# Pixel1_0_0.net
KiCad netlist of a schematic drawn in Altium Designer
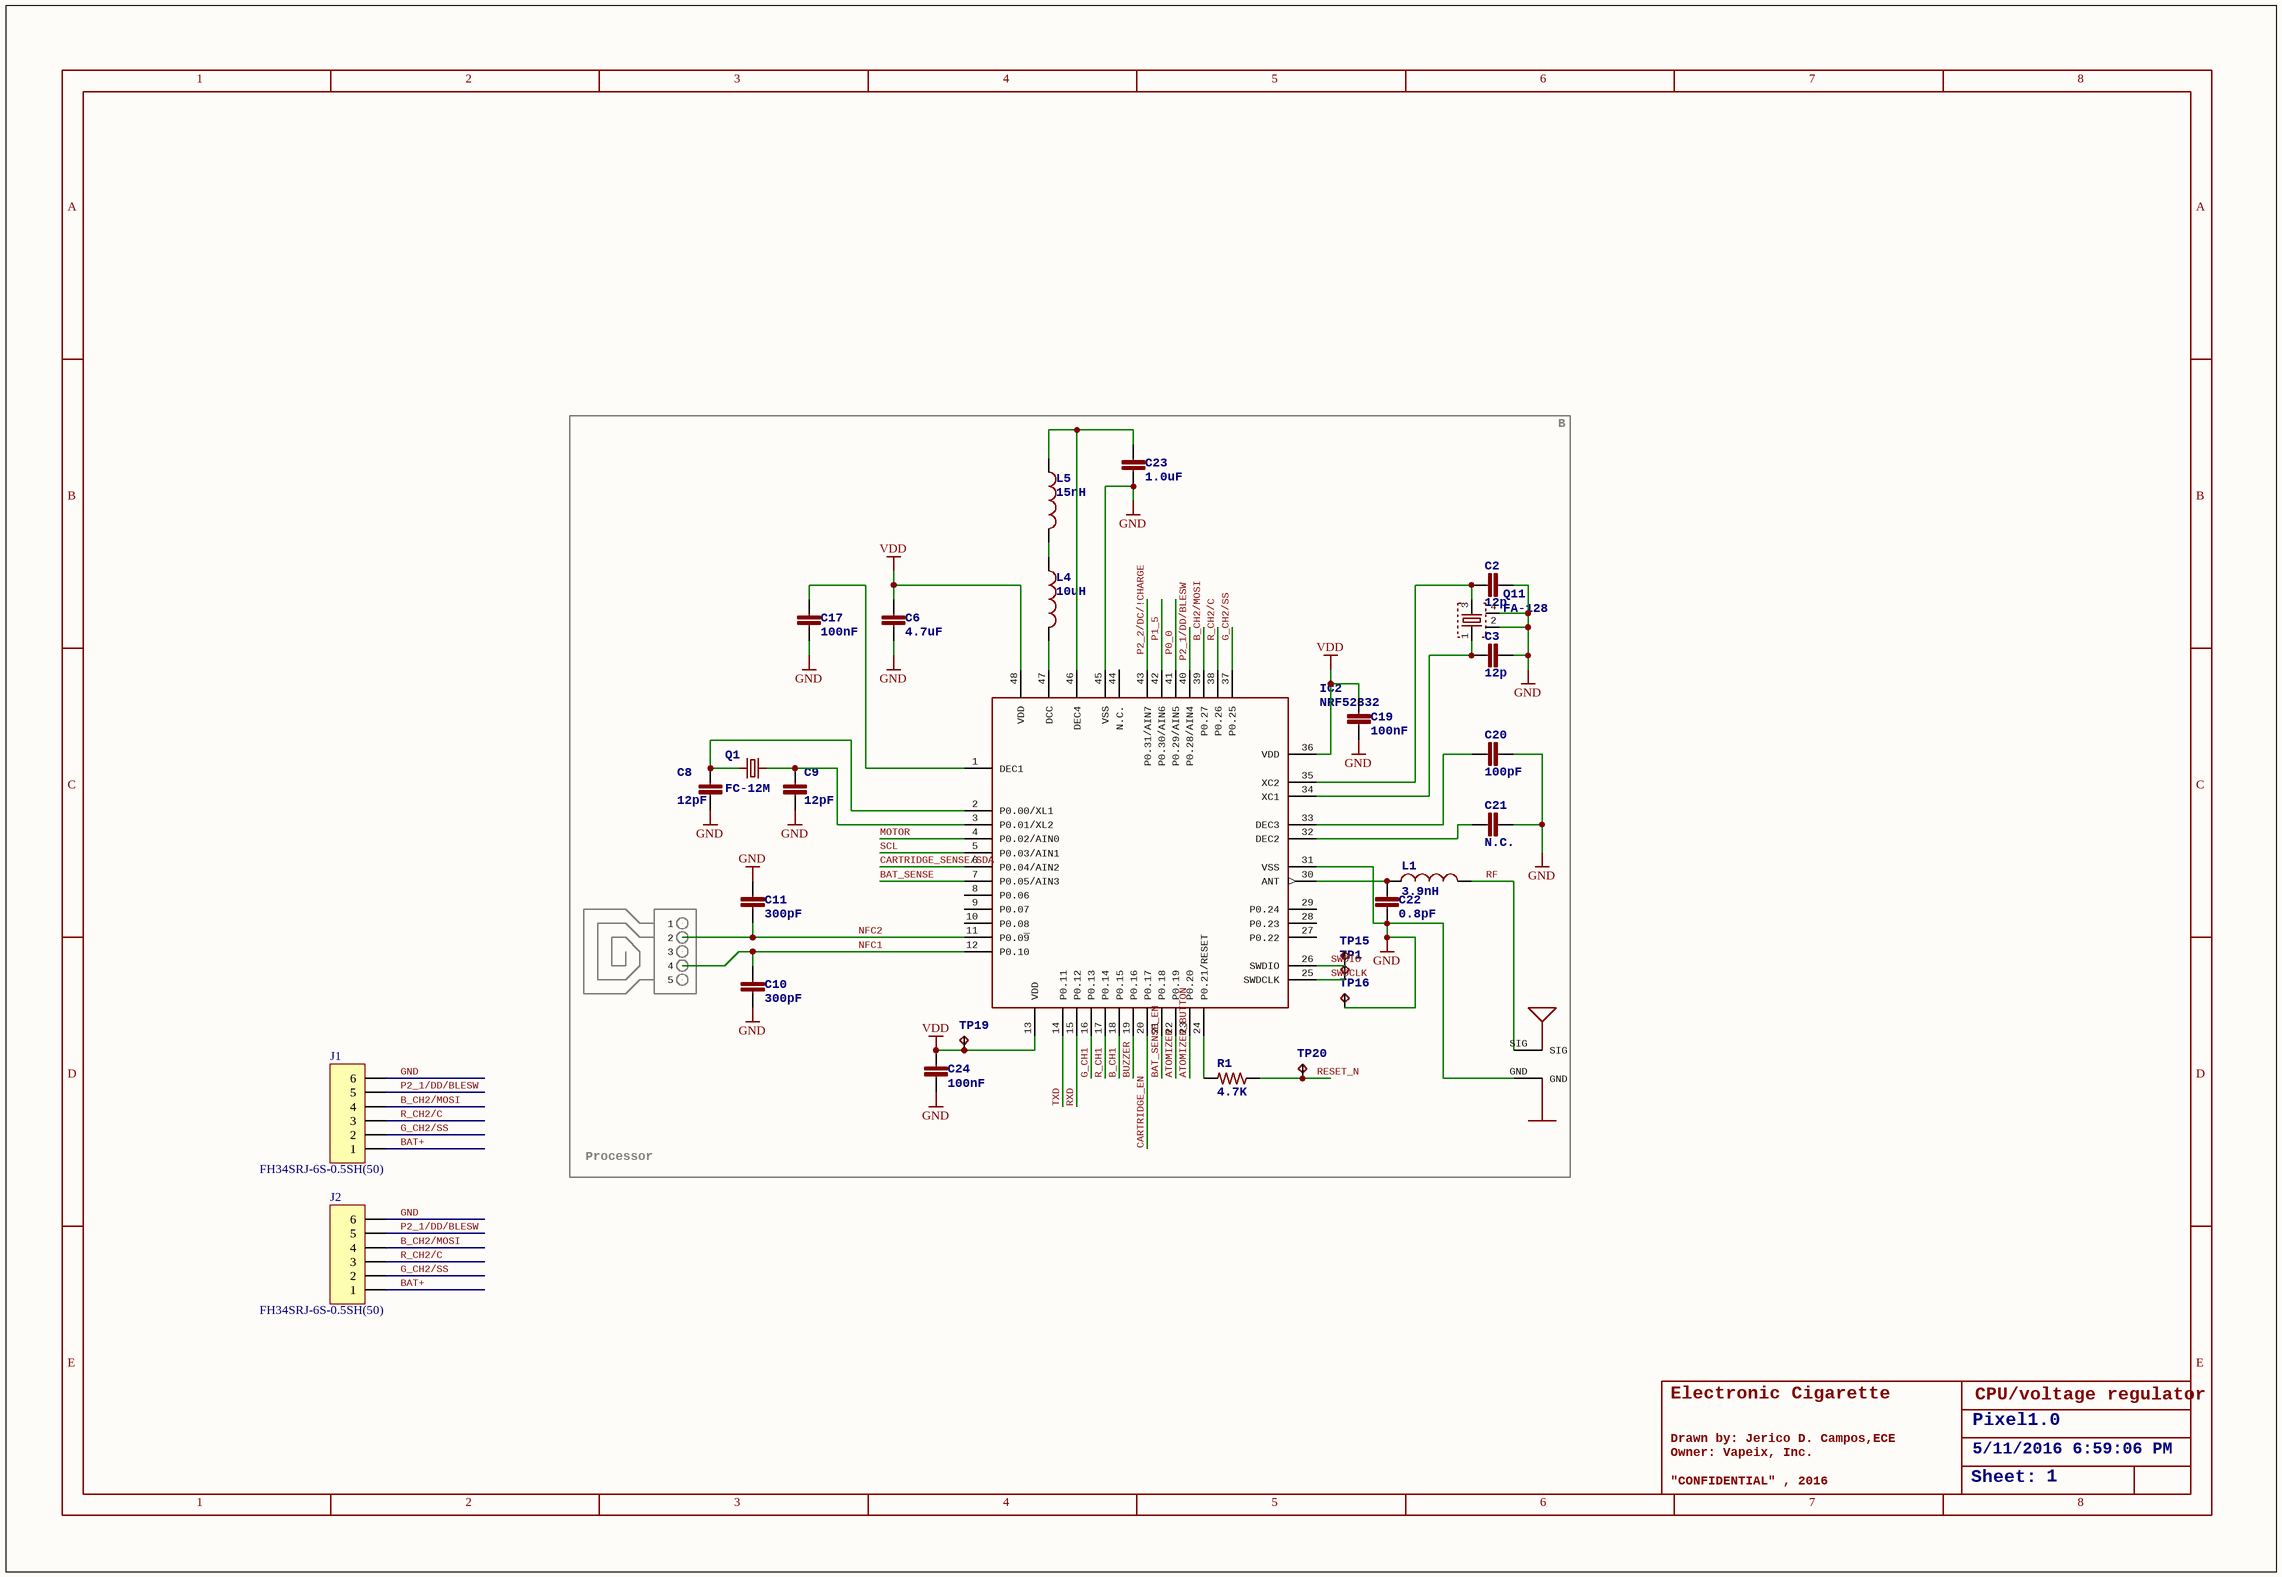
[diagram p0: Pixel1.0_0.SchDoc]

(export (version "E")
  (design (tool "Eeschema 10.0.6"))
  (components
    (comp (ref "ANT") (value "U.FL") (footprint "U.FL") (libsource (lib "Pixel1.0") (part "U.FL")))
    (comp (ref "C2")
      (value "12p")
      (footprint "C0201")
      (description "CAPACITOR, European symbol")
      (libsource (lib "") (part "C-EUC0201_2"))
    )
    (comp (ref "C3")
      (value "12p")
      (footprint "C0201")
      (description "CAPACITOR, European symbol")
      (libsource (lib "rcl") (part "C-EUC0201"))
    )
    (comp (ref "C6")
      (value "4.7uF")
      (footprint "C0201")
      (description "CAPACITOR, European symbol")
      (libsource (lib "") (part "C-EUC0201_1"))
    )
    (comp (ref "C8")
      (value "12pF")
      (footprint "C0201")
      (description "CAPACITOR, European symbol")
      (libsource (lib "") (part "C-EUC0201_1"))
    )
    (comp (ref "C9")
      (value "12pF")
      (footprint "C0201")
      (description "CAPACITOR, European symbol")
      (libsource (lib "") (part "C-EUC0201_1"))
    )
    (comp (ref "C10")
      (value "300pF")
      (footprint "C0201")
      (description "CAPACITOR, European symbol")
      (libsource (lib "") (part "C-EUC0201_1"))
    )
    (comp (ref "C11")
      (value "300pF")
      (footprint "C0201")
      (description "CAPACITOR, European symbol")
      (libsource (lib "") (part "C-EUC0201_3"))
    )
    (comp (ref "C17")
      (value "100nF")
      (footprint "C0201")
      (description "CAPACITOR, European symbol")
      (libsource (lib "") (part "C-EUC0201_1"))
    )
    (comp (ref "C19")
      (value "100nF")
      (footprint "C0201")
      (description "CAPACITOR, European symbol")
      (libsource (lib "") (part "C-EUC0201_1"))
    )
    (comp (ref "C20")
      (value "100pF")
      (footprint "C0201")
      (description "CAPACITOR, European symbol")
      (libsource (lib "rcl") (part "C-EUC0201"))
    )
    (comp (ref "C21")
      (value "N.C.")
      (footprint "C0201")
      (description "CAPACITOR, European symbol")
      (libsource (lib "rcl") (part "C-EUC0201"))
    )
    (comp (ref "C22")
      (value "0.8pF")
      (footprint "C0201")
      (description "CAPACITOR, European symbol")
      (libsource (lib "") (part "C-EUC0201_1"))
    )
    (comp (ref "C23")
      (value "1.0uF")
      (footprint "C0201")
      (description "CAPACITOR, European symbol")
      (libsource (lib "") (part "C-EUC0201_1"))
    )
    (comp (ref "C24")
      (value "100nF")
      (footprint "C0201")
      (description "CAPACITOR, European symbol")
      (libsource (lib "") (part "C-EUC0201_1"))
    )
    (comp (ref "IC2") (value "NRF52832") (footprint "QFN-48") (libsource (lib "FTDI") (part "NRF52832")))
    (comp (ref "J1")
      (value "FH34SRJ-6S-0.5SH(50)")
      (footprint "59453061110ECHLF")
      (description "WR-FPC 0.50mm SMT ZIF Horizontal Bottom Contact")
      (fields
        (field (name "MANUFACTURER") "Würth Elektronik eiSos GmbH")
        (field (name "PARTNO") "68710614522")
        (field (name "CREATED BY") "Karrer Zheng")
      )
      (libsource (lib "Components") (part "WE-ZIF Connector WR-FPC 68710614522"))
    )
    (comp (ref "J2")
      (value "FH34SRJ-6S-0.5SH(50)")
      (footprint "59453061110ECHLF")
      (description "WR-FPC 0.50mm SMT ZIF Horizontal Bottom Contact")
      (fields
        (field (name "MANUFACTURER") "Würth Elektronik eiSos GmbH")
        (field (name "PARTNO") "68710614522")
        (field (name "CREATED BY") "Karrer Zheng")
      )
      (libsource (lib "Components") (part "WE-ZIF Connector WR-FPC 68710614522"))
    )
    (comp (ref "L1") (value "3.9nH") (footprint "JE0402") (libsource (lib "vapeix") (part "LBEAD")))
    (comp (ref "L4") (value "10uH") (footprint "JE0402") (libsource (lib "vapeix") (part "LBEAD")))
    (comp (ref "L5") (value "15nH") (footprint "JE0402") (libsource (lib "vapeix") (part "LBEAD")))
    (comp (ref "Q1")
      (value "FC-12M")
      (footprint "FC-12M")
      (description "kHz RANGE CRYSTAL UNIT   LOW PROFILE SMDSource: Epson Toyocom FC-12M.pdf")
      (libsource (lib "crystal") (part "FC-12M"))
    )
    (comp (ref "Q11")
      (value "FA-128")
      (footprint "FA-128")
      (description "MHz RANGE CRYSTAL UNIT    Source: Epson Toyocom")
      (libsource (lib "crystal") (part "FA-128"))
    )
    (comp (ref "R1")
      (value "4.7K")
      (footprint "R0201")
      (description "RESISTOR, American symbol")
      (libsource (lib "rcl") (part "R-US_R0201"))
    )
    (comp (ref "TP1")
      (value "TPTP06R")
      (footprint "TP06R")
      (description "Test pad")
      (libsource (lib "testpad") (part "TPTP06R"))
    )
    (comp (ref "TP15")
      (value "TPTP06R")
      (footprint "TP06R")
      (description "Test pad")
      (libsource (lib "testpad") (part "TPTP06R"))
    )
    (comp (ref "TP16")
      (value "TPTP06R")
      (footprint "TP06R")
      (description "Test pad")
      (libsource (lib "testpad") (part "TPTP06R"))
    )
    (comp (ref "TP19")
      (value "TPTP06R")
      (footprint "TP06R")
      (description "Test pad")
      (libsource (lib "testpad") (part "TPTP06R"))
    )
    (comp (ref "TP20")
      (value "TPTP06R")
      (footprint "TP06R")
      (description "Test pad")
      (libsource (lib "testpad") (part "TPTP06R"))
    )
    (comp (ref "U$2")
      (value "NFCCONNECTORMOLEX_5PIN")
      (footprint "NFC.CONN")
      (libsource (lib "vapeix") (part "NFCCONNECTORMOLEX_5PIN"))
    )
  )
  (nets
    (net (code "1") (name "/ATOMIZER") (class "Default")
      (node (ref "IC2") (pin "22") (pinfunction "P0.19_22") (pintype "passive"))
    )
    (net (code "2") (name "/ATOMIZER_BUTTON") (class "Default")
      (node (ref "IC2") (pin "23") (pinfunction "P0.20_23") (pintype "passive"))
    )
    (net (code "3") (name "/BAT+") (class "Default")
      (node (ref "J1") (pin "1") (pinfunction "1_1") (pintype "passive"))
      (node (ref "J2") (pin "1") (pinfunction "1_1") (pintype "passive"))
    )
    (net (code "4") (name "/BAT_SENSE") (class "Default")
      (node (ref "IC2") (pin "7") (pinfunction "P0.05/AIN3_7") (pintype "passive"))
    )
    (net (code "5") (name "/BAT_SENSE_EN") (class "Default")
      (node (ref "IC2") (pin "21") (pinfunction "P0.18_21") (pintype "passive"))
    )
    (net (code "6") (name "/BUZZER") (class "Default")
      (node (ref "IC2") (pin "19") (pinfunction "P0.16_19") (pintype "passive"))
    )
    (net (code "7") (name "/B_CH1") (class "Default")
      (node (ref "IC2") (pin "18") (pinfunction "P0.15_18") (pintype "passive"))
    )
    (net (code "8") (name "/B_CH2{slash}MOSI") (class "Default")
      (node (ref "IC2") (pin "39") (pinfunction "P0.27_39") (pintype "passive"))
      (node (ref "J1") (pin "4") (pinfunction "4_4") (pintype "passive"))
      (node (ref "J2") (pin "4") (pinfunction "4_4") (pintype "passive"))
    )
    (net (code "9") (name "/CARTRIDGE_EN") (class "Default")
      (node (ref "IC2") (pin "20") (pinfunction "P0.17_20") (pintype "passive"))
    )
    (net (code "10") (name "/CARTRIDGE_SENSE{slash}SDA") (class "Default")
      (node (ref "IC2") (pin "6") (pinfunction "P0.04/AIN2_6") (pintype "passive"))
    )
    (net (code "11") (name "/G_CH1") (class "Default")
      (node (ref "IC2") (pin "16") (pinfunction "P0.13_16") (pintype "passive"))
    )
    (net (code "12") (name "/G_CH2{slash}SS") (class "Default")
      (node (ref "IC2") (pin "37") (pinfunction "P0.25_37") (pintype "passive"))
      (node (ref "J1") (pin "2") (pinfunction "2_2") (pintype "passive"))
      (node (ref "J2") (pin "2") (pinfunction "2_2") (pintype "passive"))
    )
    (net (code "13") (name "/MOTOR") (class "Default")
      (node (ref "IC2") (pin "4") (pinfunction "P0.02/AIN0_4") (pintype "passive"))
    )
    (net (code "14") (name "/NFC1") (class "Default")
      (node (ref "C10") (pin "1") (pinfunction "1_1") (pintype "passive"))
      (node (ref "IC2") (pin "12") (pinfunction "P0.10_12") (pintype "passive"))
      (node (ref "U$2") (pin "4") (pinfunction "4_4") (pintype "passive"))
    )
    (net (code "15") (name "/NFC2") (class "Default")
      (node (ref "C11") (pin "1") (pinfunction "1_1") (pintype "passive"))
      (node (ref "IC2") (pin "11") (pinfunction "P0.0~{9}_11") (pintype "passive"))
      (node (ref "U$2") (pin "2") (pinfunction "2_2") (pintype "passive"))
    )
    (net (code "16") (name "/P0_0") (class "Default")
      (node (ref "IC2") (pin "41") (pinfunction "P0.29/AIN5_41") (pintype "passive"))
    )
    (net (code "17") (name "/P1_5") (class "Default")
      (node (ref "IC2") (pin "42") (pinfunction "P0.30/AIN6_42") (pintype "passive"))
    )
    (net (code "18") (name "/P2_1{slash}DD{slash}BLESW") (class "Default")
      (node (ref "IC2") (pin "40") (pinfunction "P0.28/AIN4_40") (pintype "passive"))
      (node (ref "J1") (pin "5") (pinfunction "5_5") (pintype "passive"))
      (node (ref "J2") (pin "5") (pinfunction "5_5") (pintype "passive"))
    )
    (net (code "19") (name "/P2_2{slash}DC{slash}!CHARGE") (class "Default")
      (node (ref "IC2") (pin "43") (pinfunction "P0.31/AIN7_43") (pintype "passive"))
    )
    (net (code "20") (name "/RESET_N") (class "Default")
      (node (ref "R1") (pin "1") (pinfunction "1_1") (pintype "passive"))
      (node (ref "TP20") (pin "TP") (pinfunction "TP_TP") (pintype "passive"))
    )
    (net (code "21") (name "/RF") (class "Default")
      (node (ref "ANT") (pin "SIG") (pinfunction "SIG_SIG") (pintype "passive"))
      (node (ref "L1") (pin "2") (pinfunction "2_2") (pintype "passive"))
    )
    (net (code "22") (name "/RXD") (class "Default")
      (node (ref "IC2") (pin "15") (pinfunction "P0.12_15") (pintype "passive"))
    )
    (net (code "23") (name "/R_CH1") (class "Default")
      (node (ref "IC2") (pin "17") (pinfunction "P0.14_17") (pintype "passive"))
    )
    (net (code "24") (name "/R_CH2{slash}C") (class "Default")
      (node (ref "IC2") (pin "38") (pinfunction "P0.26_38") (pintype "passive"))
      (node (ref "J1") (pin "3") (pinfunction "3_3") (pintype "passive"))
      (node (ref "J2") (pin "3") (pinfunction "3_3") (pintype "passive"))
    )
    (net (code "25") (name "/SCL") (class "Default")
      (node (ref "IC2") (pin "5") (pinfunction "P0.03/AIN1_5") (pintype "passive"))
    )
    (net (code "26") (name "/SWDCLK") (class "Default")
      (node (ref "IC2") (pin "25") (pinfunction "SWDCLK_25") (pintype "open_collector"))
      (node (ref "TP1") (pin "TP") (pinfunction "TP_TP") (pintype "passive"))
    )
    (net (code "27") (name "/SWDIO") (class "Default")
      (node (ref "IC2") (pin "26") (pinfunction "SWDIO_26") (pintype "open_collector"))
      (node (ref "TP15") (pin "TP") (pinfunction "TP_TP") (pintype "passive"))
    )
    (net (code "28") (name "/TXD") (class "Default")
      (node (ref "IC2") (pin "14") (pinfunction "P0.11_14") (pintype "passive"))
    )
    (net (code "29") (name "GND") (class "Default")
      (node (ref "ANT") (pin "GND") (pinfunction "GND_GND") (pintype "passive"))
      (node (ref "C10") (pin "2") (pinfunction "2_2") (pintype "passive"))
      (node (ref "C11") (pin "2") (pinfunction "2_2") (pintype "passive"))
      (node (ref "C17") (pin "2") (pinfunction "2_2") (pintype "passive"))
      (node (ref "C19") (pin "2") (pinfunction "2_2") (pintype "passive"))
      (node (ref "C2") (pin "2") (pinfunction "2_2") (pintype "passive"))
      (node (ref "C20") (pin "1") (pinfunction "1_1") (pintype "passive"))
      (node (ref "C21") (pin "1") (pinfunction "1_1") (pintype "passive"))
      (node (ref "C22") (pin "2") (pinfunction "2_2") (pintype "passive"))
      (node (ref "C23") (pin "2") (pinfunction "2_2") (pintype "passive"))
      (node (ref "C24") (pin "2") (pinfunction "2_2") (pintype "passive"))
      (node (ref "C3") (pin "1") (pinfunction "1_1") (pintype "passive"))
      (node (ref "C6") (pin "2") (pinfunction "2_2") (pintype "passive"))
      (node (ref "C8") (pin "2") (pinfunction "2_2") (pintype "passive"))
      (node (ref "C9") (pin "2") (pinfunction "2_2") (pintype "passive"))
      (node (ref "IC2") (pin "31") (pinfunction "VSS_31") (pintype "power_in"))
      (node (ref "IC2") (pin "45") (pinfunction "VSS_45") (pintype "power_in"))
      (node (ref "J1") (pin "6") (pinfunction "6_6") (pintype "passive"))
      (node (ref "J2") (pin "6") (pinfunction "6_6") (pintype "passive"))
      (node (ref "Q11") (pin "2") (pinfunction "2_2") (pintype "passive"))
      (node (ref "Q11") (pin "4") (pinfunction "4_4") (pintype "passive"))
      (node (ref "TP16") (pin "TP") (pinfunction "TP_TP") (pintype "passive"))
    )
    (net (code "30") (name "Net-(IC2-ANT)") (class "Default")
      (node (ref "C22") (pin "1") (pinfunction "1_1") (pintype "passive"))
      (node (ref "IC2") (pin "30") (pinfunction "ANT_30") (pintype "output"))
      (node (ref "L1") (pin "1") (pinfunction "1_1") (pintype "passive"))
    )
    (net (code "31") (name "Net-(IC2-DCC)") (class "Default")
      (node (ref "IC2") (pin "47") (pinfunction "DCC_47") (pintype "power_in"))
      (node (ref "L4") (pin "2") (pinfunction "2_2") (pintype "passive"))
    )
    (net (code "32") (name "Net-(IC2-DEC1)") (class "Default")
      (node (ref "C17") (pin "1") (pinfunction "1_1") (pintype "passive"))
      (node (ref "IC2") (pin "1") (pinfunction "DEC1_1") (pintype "power_in"))
    )
    (net (code "33") (name "Net-(IC2-DEC2)") (class "Default")
      (node (ref "C21") (pin "2") (pinfunction "2_2") (pintype "passive"))
      (node (ref "IC2") (pin "32") (pinfunction "DEC2_32") (pintype "power_in"))
    )
    (net (code "34") (name "Net-(IC2-DEC3)") (class "Default")
      (node (ref "C20") (pin "2") (pinfunction "2_2") (pintype "passive"))
      (node (ref "IC2") (pin "33") (pinfunction "DEC3_33") (pintype "power_in"))
    )
    (net (code "35") (name "Net-(IC2-DEC4)") (class "Default")
      (node (ref "C23") (pin "1") (pinfunction "1_1") (pintype "passive"))
      (node (ref "IC2") (pin "46") (pinfunction "DEC4_46") (pintype "power_in"))
      (node (ref "L5") (pin "1") (pinfunction "1_1") (pintype "passive"))
    )
    (net (code "36") (name "Net-(IC2-P0.00{slash}XL1)") (class "Default")
      (node (ref "C8") (pin "1") (pinfunction "1_1") (pintype "passive"))
      (node (ref "IC2") (pin "2") (pinfunction "P0.00/XL1_2") (pintype "passive"))
      (node (ref "Q1") (pin "1") (pinfunction "1_1") (pintype "passive"))
    )
    (net (code "37") (name "Net-(IC2-P0.01{slash}XL2)") (class "Default")
      (node (ref "C9") (pin "1") (pinfunction "1_1") (pintype "passive"))
      (node (ref "IC2") (pin "3") (pinfunction "P0.01/XL2_3") (pintype "passive"))
      (node (ref "Q1") (pin "2") (pinfunction "2_2") (pintype "passive"))
    )
    (net (code "38") (name "Net-(IC2-P0.21{slash}RESET)") (class "Default")
      (node (ref "IC2") (pin "24") (pinfunction "P0.21/RESET_24") (pintype "passive"))
      (node (ref "R1") (pin "2") (pinfunction "2_2") (pintype "passive"))
    )
    (net (code "39") (name "Net-(IC2-XC1)") (class "Default")
      (node (ref "C3") (pin "2") (pinfunction "2_2") (pintype "passive"))
      (node (ref "IC2") (pin "34") (pinfunction "XC1_34") (pintype "open_collector"))
      (node (ref "Q11") (pin "1") (pinfunction "1_1") (pintype "passive"))
    )
    (net (code "40") (name "Net-(IC2-XC2)") (class "Default")
      (node (ref "C2") (pin "1") (pinfunction "1_1") (pintype "passive"))
      (node (ref "IC2") (pin "35") (pinfunction "XC2_35") (pintype "open_collector"))
      (node (ref "Q11") (pin "3") (pinfunction "3_3") (pintype "passive"))
    )
    (net (code "41") (name "Net-(L4-Pad1)") (class "Default")
      (node (ref "L4") (pin "1") (pinfunction "1_1") (pintype "passive"))
      (node (ref "L5") (pin "2") (pinfunction "2_2") (pintype "passive"))
    )
    (net (code "42") (name "VDD") (class "Default")
      (node (ref "C19") (pin "1") (pinfunction "1_1") (pintype "passive"))
      (node (ref "C24") (pin "1") (pinfunction "1_1") (pintype "passive"))
      (node (ref "C6") (pin "1") (pinfunction "1_1") (pintype "passive"))
      (node (ref "IC2") (pin "13") (pinfunction "VDD_13") (pintype "passive"))
      (node (ref "IC2") (pin "36") (pinfunction "VDD_36") (pintype "power_in"))
      (node (ref "IC2") (pin "48") (pinfunction "VDD_48") (pintype "power_in"))
      (node (ref "TP19") (pin "TP") (pinfunction "TP_TP") (pintype "passive"))
    )
    (net (code "43") (name "unconnected-(IC2-N.C.-Pad44)") (class "Default")
      (node (ref "IC2") (pin "44") (pinfunction "N.C._44") (pintype "passive"))
    )
    (net (code "44") (name "unconnected-(IC2-P0.06-Pad8)") (class "Default")
      (node (ref "IC2") (pin "8") (pinfunction "P0.06_8") (pintype "passive"))
    )
    (net (code "45") (name "unconnected-(IC2-P0.07-Pad9)") (class "Default")
      (node (ref "IC2") (pin "9") (pinfunction "P0.07_9") (pintype "passive"))
    )
    (net (code "46") (name "unconnected-(IC2-P0.08-Pad10)") (class "Default")
      (node (ref "IC2") (pin "10") (pinfunction "P0.08_10") (pintype "passive"))
    )
    (net (code "47") (name "unconnected-(IC2-P0.22-Pad27)") (class "Default")
      (node (ref "IC2") (pin "27") (pinfunction "P0.22_27") (pintype "passive"))
    )
    (net (code "48") (name "unconnected-(IC2-P0.23-Pad28)") (class "Default")
      (node (ref "IC2") (pin "28") (pinfunction "P0.23_28") (pintype "passive"))
    )
    (net (code "49") (name "unconnected-(IC2-P0.24-Pad29)") (class "Default")
      (node (ref "IC2") (pin "29") (pinfunction "P0.24_29") (pintype "passive"))
    )
    (net (code "50") (name "unconnected-(U$2-Pad1)") (class "Default")
      (node (ref "U$2") (pin "1") (pinfunction "1_1") (pintype "passive"))
    )
    (net (code "51") (name "unconnected-(U$2-Pad3)") (class "Default")
      (node (ref "U$2") (pin "3") (pinfunction "3_3") (pintype "passive"))
    )
    (net (code "52") (name "unconnected-(U$2-Pad5)") (class "Default")
      (node (ref "U$2") (pin "5") (pinfunction "5_5") (pintype "passive"))
    )
  )
)
